# reciever.net
KiCad netlist of a schematic drawn in EAGLE
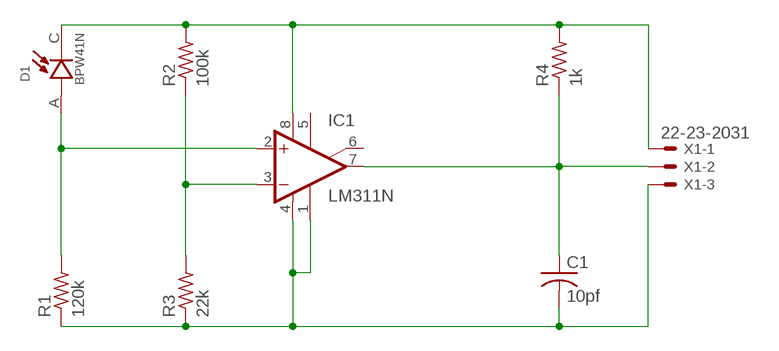
[diagram p0: schematic, sheet 1]

(export (version "E")
  (design (tool "Eeschema 10.0.6"))
  (components
    (comp (ref "C1")
      (value "10pf")
      (footprint "eagle-import:C025-024X044")
      (libsource (lib "eagle-import") (part "C-US025-024X044"))
    )
    (comp (ref "D1")
      (value "BPW41N")
      (footprint "eagle-import:DIO_BPW41N")
      (fields (field (name "MF") "Vishay Semiconductor Opto Division"))
      (libsource (lib "eagle-import") (part "BPW41N"))
    )
    (comp (ref "IC1")
      (value "LM311N")
      (footprint "eagle-import:DIL08")
      (libsource (lib "eagle-import") (part "LM311N"))
    )
    (comp (ref "R1")
      (value "120k")
      (footprint "eagle-import:0204_5")
      (libsource (lib "eagle-import") (part "R-US_0204/5"))
    )
    (comp (ref "R2")
      (value "100k")
      (footprint "eagle-import:0204_5")
      (libsource (lib "eagle-import") (part "R-US_0204/5"))
    )
    (comp (ref "R3")
      (value "22k")
      (footprint "eagle-import:0204_5")
      (libsource (lib "eagle-import") (part "R-US_0204/5"))
    )
    (comp (ref "R4")
      (value "1k")
      (footprint "eagle-import:0204_5")
      (libsource (lib "eagle-import") (part "R-US_0204/5"))
    )
    (comp (ref "X1")
      (value "22-23-2031")
      (footprint "eagle-import:22-23-2031")
      (fields (field (name "MF") "MOLEX"))
      (libsource (lib "eagle-import") (part "22-23-2031"))
    )
  )
  (nets
    (net (code "1") (name "Net-(IC1-+IN)") (class "Default")
      (node (ref "D1") (pin "A") (pinfunction "A_A") (pintype "passive"))
      (node (ref "IC1") (pin "2") (pinfunction "+IN_2") (pintype "input"))
      (node (ref "R1") (pin "2") (pinfunction "2_2") (pintype "passive"))
    )
    (net (code "2") (name "Net-(IC1--IN)") (class "Default")
      (node (ref "IC1") (pin "3") (pinfunction "-IN_3") (pintype "input"))
      (node (ref "R2") (pin "1") (pinfunction "1_1") (pintype "passive"))
      (node (ref "R3") (pin "2") (pinfunction "2_2") (pintype "passive"))
    )
    (net (code "3") (name "Net-(IC1-GND)") (class "Default")
      (node (ref "C1") (pin "2") (pinfunction "2_2") (pintype "passive"))
      (node (ref "IC1") (pin "1") (pinfunction "GND_1") (pintype "passive"))
      (node (ref "IC1") (pin "4") (pinfunction "V-_4") (pintype "power_in"))
      (node (ref "R1") (pin "1") (pinfunction "1_1") (pintype "passive"))
      (node (ref "R3") (pin "1") (pinfunction "1_1") (pintype "passive"))
      (node (ref "X1") (pin "3") (pinfunction "S_3") (pintype "passive"))
    )
    (net (code "4") (name "Net-(IC1-OUT)") (class "Default")
      (node (ref "C1") (pin "1") (pinfunction "1_1") (pintype "passive"))
      (node (ref "IC1") (pin "7") (pinfunction "OUT_7") (pintype "output"))
      (node (ref "R4") (pin "1") (pinfunction "1_1") (pintype "passive"))
      (node (ref "X1") (pin "2") (pinfunction "S_2") (pintype "passive"))
    )
    (net (code "5") (name "Net-(IC1-V+)") (class "Default")
      (node (ref "D1") (pin "C") (pinfunction "C_C") (pintype "passive"))
      (node (ref "IC1") (pin "8") (pinfunction "V+_8") (pintype "power_in"))
      (node (ref "R2") (pin "2") (pinfunction "2_2") (pintype "passive"))
      (node (ref "R4") (pin "2") (pinfunction "2_2") (pintype "passive"))
      (node (ref "X1") (pin "1") (pinfunction "S_1") (pintype "passive"))
    )
    (net (code "6") (name "unconnected-(IC1-ON-Pad5)") (class "Default")
      (node (ref "IC1") (pin "5") (pinfunction "ON_5") (pintype "passive"))
    )
    (net (code "7") (name "unconnected-(IC1-ON{slash}STR-Pad6)") (class "Default")
      (node (ref "IC1") (pin "6") (pinfunction "ON/STR_6") (pintype "passive"))
    )
  )
)
